# 5_ETH.net
KiCad netlist of a schematic drawn in Altium Designer
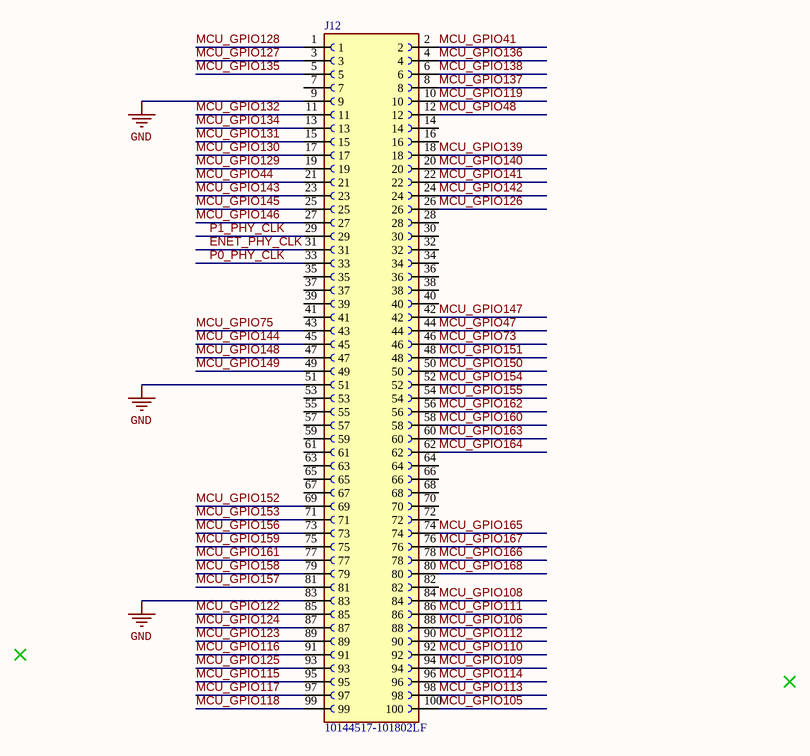
[diagram p0: 5.ETH.SchDoc]

(export (version "E")
  (design (tool "Eeschema 10.0.6"))
  (components
    (comp (ref "J12")
      (value "10144517-101802LF")
      (footprint "AMPHENOL_10144517-101802LF")
      (fields (field (name "MF") "AMPHENOL ICC / FCI"))
      (libsource (lib "PEETS_V2") (part "10144517-101802LF"))
    )
  )
  (nets
    (net (code "1") (name "/ENET_PHY_CLK") (class "Default")
      (node (ref "J12") (pin "31") (pinfunction "31_31") (pintype "passive"))
    )
    (net (code "2") (name "/MCU_GPIO41") (class "Default")
      (node (ref "J12") (pin "2") (pinfunction "2_2") (pintype "passive"))
    )
    (net (code "3") (name "/MCU_GPIO44") (class "Default")
      (node (ref "J12") (pin "21") (pinfunction "21_21") (pintype "passive"))
    )
    (net (code "4") (name "/MCU_GPIO47") (class "Default")
      (node (ref "J12") (pin "44") (pinfunction "44_44") (pintype "passive"))
    )
    (net (code "5") (name "/MCU_GPIO48") (class "Default")
      (node (ref "J12") (pin "12") (pinfunction "12_12") (pintype "passive"))
    )
    (net (code "6") (name "/MCU_GPIO73") (class "Default")
      (node (ref "J12") (pin "46") (pinfunction "46_46") (pintype "passive"))
    )
    (net (code "7") (name "/MCU_GPIO75") (class "Default")
      (node (ref "J12") (pin "43") (pinfunction "43_43") (pintype "passive"))
    )
    (net (code "8") (name "/MCU_GPIO105") (class "Default")
      (node (ref "J12") (pin "100") (pinfunction "100_100") (pintype "passive"))
    )
    (net (code "9") (name "/MCU_GPIO106") (class "Default")
      (node (ref "J12") (pin "88") (pinfunction "88_88") (pintype "passive"))
    )
    (net (code "10") (name "/MCU_GPIO108") (class "Default")
      (node (ref "J12") (pin "84") (pinfunction "84_84") (pintype "passive"))
    )
    (net (code "11") (name "/MCU_GPIO109") (class "Default")
      (node (ref "J12") (pin "94") (pinfunction "94_94") (pintype "passive"))
    )
    (net (code "12") (name "/MCU_GPIO110") (class "Default")
      (node (ref "J12") (pin "92") (pinfunction "92_92") (pintype "passive"))
    )
    (net (code "13") (name "/MCU_GPIO111") (class "Default")
      (node (ref "J12") (pin "86") (pinfunction "86_86") (pintype "passive"))
    )
    (net (code "14") (name "/MCU_GPIO112") (class "Default")
      (node (ref "J12") (pin "90") (pinfunction "90_90") (pintype "passive"))
    )
    (net (code "15") (name "/MCU_GPIO113") (class "Default")
      (node (ref "J12") (pin "98") (pinfunction "98_98") (pintype "passive"))
    )
    (net (code "16") (name "/MCU_GPIO114") (class "Default")
      (node (ref "J12") (pin "96") (pinfunction "96_96") (pintype "passive"))
    )
    (net (code "17") (name "/MCU_GPIO115") (class "Default")
      (node (ref "J12") (pin "95") (pinfunction "95_95") (pintype "passive"))
    )
    (net (code "18") (name "/MCU_GPIO116") (class "Default")
      (node (ref "J12") (pin "91") (pinfunction "91_91") (pintype "passive"))
    )
    (net (code "19") (name "/MCU_GPIO117") (class "Default")
      (node (ref "J12") (pin "97") (pinfunction "97_97") (pintype "passive"))
    )
    (net (code "20") (name "/MCU_GPIO118") (class "Default")
      (node (ref "J12") (pin "99") (pinfunction "99_99") (pintype "passive"))
    )
    (net (code "21") (name "/MCU_GPIO119") (class "Default")
      (node (ref "J12") (pin "10") (pinfunction "10_10") (pintype "passive"))
    )
    (net (code "22") (name "/MCU_GPIO122") (class "Default")
      (node (ref "J12") (pin "85") (pinfunction "85_85") (pintype "passive"))
    )
    (net (code "23") (name "/MCU_GPIO123") (class "Default")
      (node (ref "J12") (pin "89") (pinfunction "89_89") (pintype "passive"))
    )
    (net (code "24") (name "/MCU_GPIO124") (class "Default")
      (node (ref "J12") (pin "87") (pinfunction "87_87") (pintype "passive"))
    )
    (net (code "25") (name "/MCU_GPIO125") (class "Default")
      (node (ref "J12") (pin "93") (pinfunction "93_93") (pintype "passive"))
    )
    (net (code "26") (name "/MCU_GPIO126") (class "Default")
      (node (ref "J12") (pin "26") (pinfunction "26_26") (pintype "passive"))
    )
    (net (code "27") (name "/MCU_GPIO127") (class "Default")
      (node (ref "J12") (pin "3") (pinfunction "3_3") (pintype "passive"))
    )
    (net (code "28") (name "/MCU_GPIO128") (class "Default")
      (node (ref "J12") (pin "1") (pinfunction "1_1") (pintype "passive"))
    )
    (net (code "29") (name "/MCU_GPIO129") (class "Default")
      (node (ref "J12") (pin "19") (pinfunction "19_19") (pintype "passive"))
    )
    (net (code "30") (name "/MCU_GPIO130") (class "Default")
      (node (ref "J12") (pin "17") (pinfunction "17_17") (pintype "passive"))
    )
    (net (code "31") (name "/MCU_GPIO131") (class "Default")
      (node (ref "J12") (pin "15") (pinfunction "15_15") (pintype "passive"))
    )
    (net (code "32") (name "/MCU_GPIO132") (class "Default")
      (node (ref "J12") (pin "11") (pinfunction "11_11") (pintype "passive"))
    )
    (net (code "33") (name "/MCU_GPIO134") (class "Default")
      (node (ref "J12") (pin "13") (pinfunction "13_13") (pintype "passive"))
    )
    (net (code "34") (name "/MCU_GPIO135") (class "Default")
      (node (ref "J12") (pin "5") (pinfunction "5_5") (pintype "passive"))
    )
    (net (code "35") (name "/MCU_GPIO136") (class "Default")
      (node (ref "J12") (pin "4") (pinfunction "4_4") (pintype "passive"))
    )
    (net (code "36") (name "/MCU_GPIO137") (class "Default")
      (node (ref "J12") (pin "8") (pinfunction "8_8") (pintype "passive"))
    )
    (net (code "37") (name "/MCU_GPIO138") (class "Default")
      (node (ref "J12") (pin "6") (pinfunction "6_6") (pintype "passive"))
    )
    (net (code "38") (name "/MCU_GPIO139") (class "Default")
      (node (ref "J12") (pin "18") (pinfunction "18_18") (pintype "passive"))
    )
    (net (code "39") (name "/MCU_GPIO140") (class "Default")
      (node (ref "J12") (pin "20") (pinfunction "20_20") (pintype "passive"))
    )
    (net (code "40") (name "/MCU_GPIO141") (class "Default")
      (node (ref "J12") (pin "22") (pinfunction "22_22") (pintype "passive"))
    )
    (net (code "41") (name "/MCU_GPIO142") (class "Default")
      (node (ref "J12") (pin "24") (pinfunction "24_24") (pintype "passive"))
    )
    (net (code "42") (name "/MCU_GPIO143") (class "Default")
      (node (ref "J12") (pin "23") (pinfunction "23_23") (pintype "passive"))
    )
    (net (code "43") (name "/MCU_GPIO144") (class "Default")
      (node (ref "J12") (pin "45") (pinfunction "45_45") (pintype "passive"))
    )
    (net (code "44") (name "/MCU_GPIO145") (class "Default")
      (node (ref "J12") (pin "25") (pinfunction "25_25") (pintype "passive"))
    )
    (net (code "45") (name "/MCU_GPIO146") (class "Default")
      (node (ref "J12") (pin "27") (pinfunction "27_27") (pintype "passive"))
    )
    (net (code "46") (name "/MCU_GPIO147") (class "Default")
      (node (ref "J12") (pin "42") (pinfunction "42_42") (pintype "passive"))
    )
    (net (code "47") (name "/MCU_GPIO148") (class "Default")
      (node (ref "J12") (pin "47") (pinfunction "47_47") (pintype "passive"))
    )
    (net (code "48") (name "/MCU_GPIO149") (class "Default")
      (node (ref "J12") (pin "49") (pinfunction "49_49") (pintype "passive"))
    )
    (net (code "49") (name "/MCU_GPIO150") (class "Default")
      (node (ref "J12") (pin "50") (pinfunction "50_50") (pintype "passive"))
    )
    (net (code "50") (name "/MCU_GPIO151") (class "Default")
      (node (ref "J12") (pin "48") (pinfunction "48_48") (pintype "passive"))
    )
    (net (code "51") (name "/MCU_GPIO152") (class "Default")
      (node (ref "J12") (pin "69") (pinfunction "69_69") (pintype "passive"))
    )
    (net (code "52") (name "/MCU_GPIO153") (class "Default")
      (node (ref "J12") (pin "71") (pinfunction "71_71") (pintype "passive"))
    )
    (net (code "53") (name "/MCU_GPIO154") (class "Default")
      (node (ref "J12") (pin "52") (pinfunction "52_52") (pintype "passive"))
    )
    (net (code "54") (name "/MCU_GPIO155") (class "Default")
      (node (ref "J12") (pin "54") (pinfunction "54_54") (pintype "passive"))
    )
    (net (code "55") (name "/MCU_GPIO156") (class "Default")
      (node (ref "J12") (pin "73") (pinfunction "73_73") (pintype "passive"))
    )
    (net (code "56") (name "/MCU_GPIO157") (class "Default")
      (node (ref "J12") (pin "81") (pinfunction "81_81") (pintype "passive"))
    )
    (net (code "57") (name "/MCU_GPIO158") (class "Default")
      (node (ref "J12") (pin "79") (pinfunction "79_79") (pintype "passive"))
    )
    (net (code "58") (name "/MCU_GPIO159") (class "Default")
      (node (ref "J12") (pin "75") (pinfunction "75_75") (pintype "passive"))
    )
    (net (code "59") (name "/MCU_GPIO160") (class "Default")
      (node (ref "J12") (pin "58") (pinfunction "58_58") (pintype "passive"))
    )
    (net (code "60") (name "/MCU_GPIO161") (class "Default")
      (node (ref "J12") (pin "77") (pinfunction "77_77") (pintype "passive"))
    )
    (net (code "61") (name "/MCU_GPIO162") (class "Default")
      (node (ref "J12") (pin "56") (pinfunction "56_56") (pintype "passive"))
    )
    (net (code "62") (name "/MCU_GPIO163") (class "Default")
      (node (ref "J12") (pin "60") (pinfunction "60_60") (pintype "passive"))
    )
    (net (code "63") (name "/MCU_GPIO164") (class "Default")
      (node (ref "J12") (pin "62") (pinfunction "62_62") (pintype "passive"))
    )
    (net (code "64") (name "/MCU_GPIO165") (class "Default")
      (node (ref "J12") (pin "74") (pinfunction "74_74") (pintype "passive"))
    )
    (net (code "65") (name "/MCU_GPIO166") (class "Default")
      (node (ref "J12") (pin "78") (pinfunction "78_78") (pintype "passive"))
    )
    (net (code "66") (name "/MCU_GPIO167") (class "Default")
      (node (ref "J12") (pin "76") (pinfunction "76_76") (pintype "passive"))
    )
    (net (code "67") (name "/MCU_GPIO168") (class "Default")
      (node (ref "J12") (pin "80") (pinfunction "80_80") (pintype "passive"))
    )
    (net (code "68") (name "/P0_PHY_CLK") (class "Default")
      (node (ref "J12") (pin "33") (pinfunction "33_33") (pintype "passive"))
    )
    (net (code "69") (name "/P1_PHY_CLK") (class "Default")
      (node (ref "J12") (pin "29") (pinfunction "29_29") (pintype "passive"))
    )
    (net (code "70") (name "GND") (class "Default")
      (node (ref "J12") (pin "51") (pinfunction "51_51") (pintype "passive"))
      (node (ref "J12") (pin "83") (pinfunction "83_83") (pintype "passive"))
      (node (ref "J12") (pin "9") (pinfunction "9_9") (pintype "passive"))
    )
    (net (code "71") (name "unconnected-(J12-Pad7)") (class "Default")
      (node (ref "J12") (pin "7") (pinfunction "7_7") (pintype "passive"))
    )
    (net (code "72") (name "unconnected-(J12-Pad14)") (class "Default")
      (node (ref "J12") (pin "14") (pinfunction "14_14") (pintype "passive"))
    )
    (net (code "73") (name "unconnected-(J12-Pad16)") (class "Default")
      (node (ref "J12") (pin "16") (pinfunction "16_16") (pintype "passive"))
    )
    (net (code "74") (name "unconnected-(J12-Pad28)") (class "Default")
      (node (ref "J12") (pin "28") (pinfunction "28_28") (pintype "passive"))
    )
    (net (code "75") (name "unconnected-(J12-Pad30)") (class "Default")
      (node (ref "J12") (pin "30") (pinfunction "30_30") (pintype "passive"))
    )
    (net (code "76") (name "unconnected-(J12-Pad32)") (class "Default")
      (node (ref "J12") (pin "32") (pinfunction "32_32") (pintype "passive"))
    )
    (net (code "77") (name "unconnected-(J12-Pad34)") (class "Default")
      (node (ref "J12") (pin "34") (pinfunction "34_34") (pintype "passive"))
    )
    (net (code "78") (name "unconnected-(J12-Pad35)") (class "Default")
      (node (ref "J12") (pin "35") (pinfunction "35_35") (pintype "passive"))
    )
    (net (code "79") (name "unconnected-(J12-Pad36)") (class "Default")
      (node (ref "J12") (pin "36") (pinfunction "36_36") (pintype "passive"))
    )
    (net (code "80") (name "unconnected-(J12-Pad37)") (class "Default")
      (node (ref "J12") (pin "37") (pinfunction "37_37") (pintype "passive"))
    )
    (net (code "81") (name "unconnected-(J12-Pad38)") (class "Default")
      (node (ref "J12") (pin "38") (pinfunction "38_38") (pintype "passive"))
    )
    (net (code "82") (name "unconnected-(J12-Pad39)") (class "Default")
      (node (ref "J12") (pin "39") (pinfunction "39_39") (pintype "passive"))
    )
    (net (code "83") (name "unconnected-(J12-Pad40)") (class "Default")
      (node (ref "J12") (pin "40") (pinfunction "40_40") (pintype "passive"))
    )
    (net (code "84") (name "unconnected-(J12-Pad41)") (class "Default")
      (node (ref "J12") (pin "41") (pinfunction "41_41") (pintype "passive"))
    )
    (net (code "85") (name "unconnected-(J12-Pad53)") (class "Default")
      (node (ref "J12") (pin "53") (pinfunction "53_53") (pintype "passive"))
    )
    (net (code "86") (name "unconnected-(J12-Pad55)") (class "Default")
      (node (ref "J12") (pin "55") (pinfunction "55_55") (pintype "passive"))
    )
    (net (code "87") (name "unconnected-(J12-Pad57)") (class "Default")
      (node (ref "J12") (pin "57") (pinfunction "57_57") (pintype "passive"))
    )
    (net (code "88") (name "unconnected-(J12-Pad59)") (class "Default")
      (node (ref "J12") (pin "59") (pinfunction "59_59") (pintype "passive"))
    )
    (net (code "89") (name "unconnected-(J12-Pad61)") (class "Default")
      (node (ref "J12") (pin "61") (pinfunction "61_61") (pintype "passive"))
    )
    (net (code "90") (name "unconnected-(J12-Pad63)") (class "Default")
      (node (ref "J12") (pin "63") (pinfunction "63_63") (pintype "passive"))
    )
    (net (code "91") (name "unconnected-(J12-Pad64)") (class "Default")
      (node (ref "J12") (pin "64") (pinfunction "64_64") (pintype "passive"))
    )
    (net (code "92") (name "unconnected-(J12-Pad65)") (class "Default")
      (node (ref "J12") (pin "65") (pinfunction "65_65") (pintype "passive"))
    )
    (net (code "93") (name "unconnected-(J12-Pad66)") (class "Default")
      (node (ref "J12") (pin "66") (pinfunction "66_66") (pintype "passive"))
    )
    (net (code "94") (name "unconnected-(J12-Pad67)") (class "Default")
      (node (ref "J12") (pin "67") (pinfunction "67_67") (pintype "passive"))
    )
    (net (code "95") (name "unconnected-(J12-Pad68)") (class "Default")
      (node (ref "J12") (pin "68") (pinfunction "68_68") (pintype "passive"))
    )
    (net (code "96") (name "unconnected-(J12-Pad70)") (class "Default")
      (node (ref "J12") (pin "70") (pinfunction "70_70") (pintype "passive"))
    )
    (net (code "97") (name "unconnected-(J12-Pad72)") (class "Default")
      (node (ref "J12") (pin "72") (pinfunction "72_72") (pintype "passive"))
    )
    (net (code "98") (name "unconnected-(J12-Pad82)") (class "Default")
      (node (ref "J12") (pin "82") (pinfunction "82_82") (pintype "passive"))
    )
  )
)
